# Eagle_DriveUnit_B-series_ver1_0.net
KiCad netlist of a schematic drawn in EAGLE
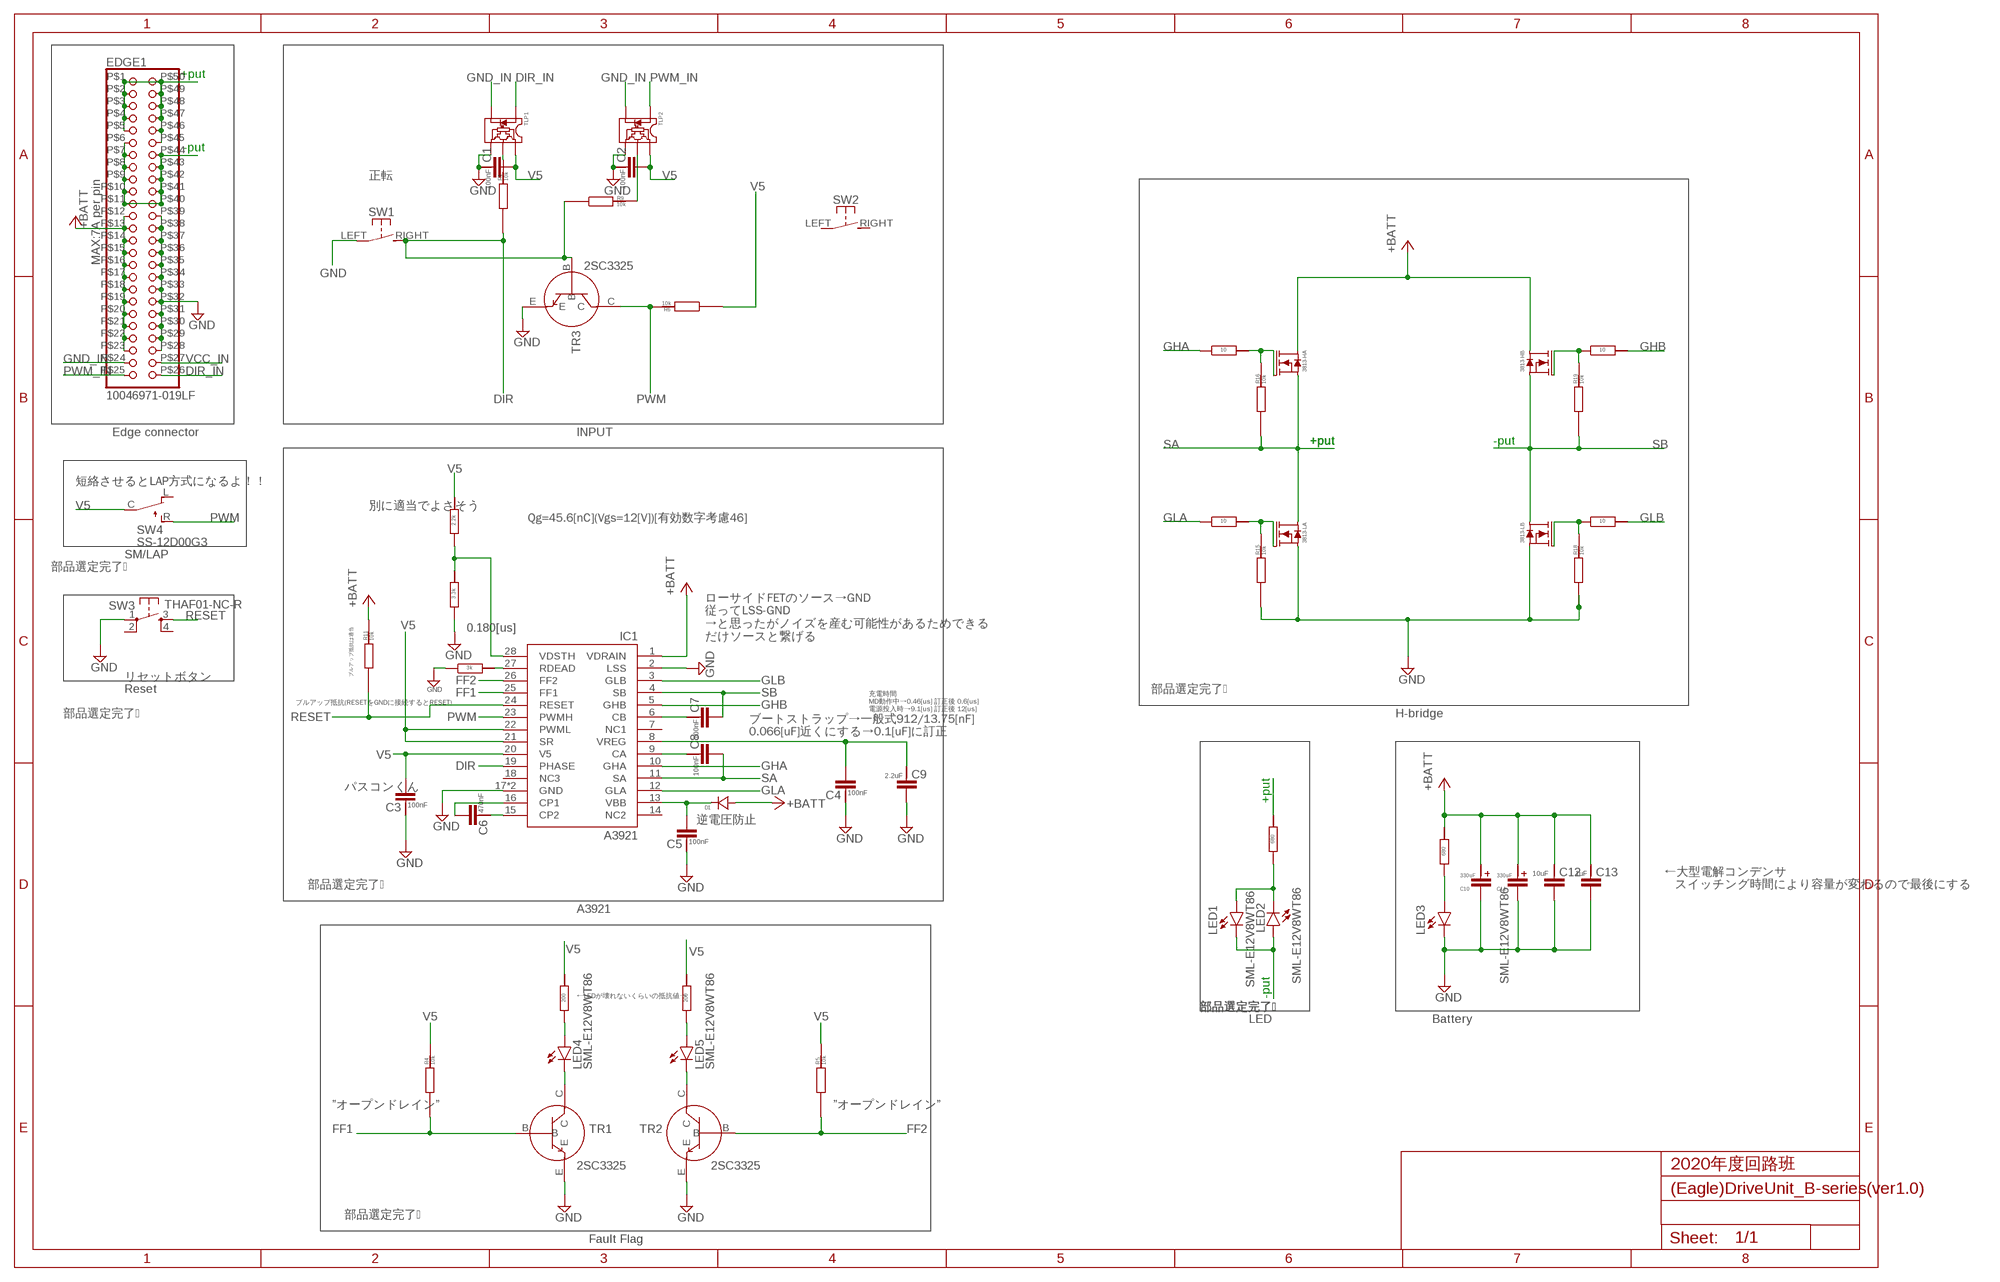
[diagram p0: schematic, sheet 1]

(export (version "E")
  (design (tool "Eeschema 10.0.6"))
  (components
    (comp (ref "3813-HA")
      (value "IRLB3813NOHOLE")
      (footprint "eagle-import:TO-220AB-NOHOLE")
      (libsource (lib "eagle-import") (part "IRLB3813NOHOLE"))
    )
    (comp (ref "3813-HB")
      (value "IRLB3813NOHOLE")
      (footprint "eagle-import:TO-220AB-NOHOLE")
      (libsource (lib "eagle-import") (part "IRLB3813NOHOLE"))
    )
    (comp (ref "3813-LA")
      (value "IRLB3813NOHOLE")
      (footprint "eagle-import:TO-220AB-NOHOLE")
      (libsource (lib "eagle-import") (part "IRLB3813NOHOLE"))
    )
    (comp (ref "3813-LB")
      (value "IRLB3813NOHOLE")
      (footprint "eagle-import:TO-220AB-NOHOLE")
      (libsource (lib "eagle-import") (part "IRLB3813NOHOLE"))
    )
    (comp (ref "C1")
      (value "GCM188L81H104KA57")
      (footprint "eagle-import:GCM188L81H104KA57")
      (libsource (lib "eagle-import") (part "GCM188L81H104KA57"))
    )
    (comp (ref "C2")
      (value "GCM188L81H104KA57")
      (footprint "eagle-import:GCM188L81H104KA57")
      (libsource (lib "eagle-import") (part "GCM188L81H104KA57"))
    )
    (comp (ref "C3")
      (value "GCM188L81H104KA57")
      (footprint "eagle-import:GCM188L81H104KA57")
      (libsource (lib "eagle-import") (part "GCM188L81H104KA57"))
    )
    (comp (ref "C4")
      (value "GCM188L81H104KA57")
      (footprint "eagle-import:GCM188L81H104KA57")
      (libsource (lib "eagle-import") (part "GCM188L81H104KA57"))
    )
    (comp (ref "C5")
      (value "GCM188L81H104KA57")
      (footprint "eagle-import:GCM188L81H104KA57")
      (libsource (lib "eagle-import") (part "GCM188L81H104KA57"))
    )
    (comp (ref "C6")
      (value "GCM21BR71H474KA55")
      (footprint "eagle-import:GCM21BR71H474KA55")
      (libsource (lib "eagle-import") (part "GCM21BR71H474KA55"))
    )
    (comp (ref "C7")
      (value "GCM188L81H104KA57")
      (footprint "eagle-import:GCM188L81H104KA57")
      (libsource (lib "eagle-import") (part "GCM188L81H104KA57"))
    )
    (comp (ref "C8")
      (value "GCM188L81H104KA57")
      (footprint "eagle-import:GCM188L81H104KA57")
      (libsource (lib "eagle-import") (part "GCM188L81H104KA57"))
    )
    (comp (ref "C9")
      (value "GRT31CC81H225KE01L")
      (footprint "eagle-import:GRT31CC81H225KE01L")
      (libsource (lib "eagle-import") (part "GRT31CC81H225KE01L"))
    )
    (comp (ref "C10")
      (value "35PZJ330M10X9")
      (footprint "eagle-import:35PZJ330M10X9")
      (libsource (lib "eagle-import") (part "35PZJ330M10X9"))
    )
    (comp (ref "C11")
      (value "35PZJ330M10X9")
      (footprint "eagle-import:35PZJ330M10X9")
      (libsource (lib "eagle-import") (part "35PZJ330M10X9"))
    )
    (comp (ref "C12")
      (value "GRM32ER7YA106KA12")
      (footprint "eagle-import:GRM32ER7YA106KA12")
      (libsource (lib "eagle-import") (part "GRM32ER7YA106KA12"))
    )
    (comp (ref "C13")
      (value "GRM21BC72A105KE01")
      (footprint "eagle-import:GRM21BC72A105KE01")
      (libsource (lib "eagle-import") (part "GRM21BC72A105KE01"))
    )
    (comp (ref "D1")
      (value "GS1010FL")
      (footprint "eagle-import:GS1010FL")
      (libsource (lib "eagle-import") (part "GS1010FL"))
    )
    (comp (ref "EDGE1")
      (value "10046971-019LF")
      (footprint "eagle-import:10046971-019LF")
      (libsource (lib "eagle-import") (part "10046971-019LF"))
    )
    (comp (ref "IC1")
      (value "A3921")
      (footprint "eagle-import:A3921")
      (libsource (lib "eagle-import") (part "A3921"))
    )
    (comp (ref "LED1")
      (value "SML-E12V8WT86")
      (footprint "eagle-import:SML-E12V8WT86")
      (libsource (lib "eagle-import") (part "SML-E12V8WT86"))
    )
    (comp (ref "LED2")
      (value "SML-E12V8WT86")
      (footprint "eagle-import:SML-E12V8WT86")
      (libsource (lib "eagle-import") (part "SML-E12V8WT86"))
    )
    (comp (ref "LED3")
      (value "SML-E12V8WT86")
      (footprint "eagle-import:SML-E12V8WT86")
      (libsource (lib "eagle-import") (part "SML-E12V8WT86"))
    )
    (comp (ref "LED4")
      (value "SML-E12V8WT86")
      (footprint "eagle-import:SML-E12V8WT86")
      (libsource (lib "eagle-import") (part "SML-E12V8WT86"))
    )
    (comp (ref "LED5")
      (value "SML-E12V8WT86")
      (footprint "eagle-import:SML-E12V8WT86")
      (libsource (lib "eagle-import") (part "SML-E12V8WT86"))
    )
    (comp (ref "R1")
      (value "RG2012")
      (footprint "eagle-import:RG2012")
      (libsource (lib "eagle-import") (part "RG2012"))
    )
    (comp (ref "R2")
      (value "RG2012N-332-W-T1")
      (footprint "eagle-import:RG2012")
      (libsource (lib "eagle-import") (part "RG2012N-332-W-T1"))
    )
    (comp (ref "R3")
      (value "RG2012P-681-B-T5")
      (footprint "eagle-import:RG2012")
      (libsource (lib "eagle-import") (part "RG2012P-681-B-T5"))
    )
    (comp (ref "R4")
      (value "RG2012")
      (footprint "eagle-import:RG2012")
      (libsource (lib "eagle-import") (part "RG2012"))
    )
    (comp (ref "R5")
      (value "RG2012")
      (footprint "eagle-import:RG2012")
      (libsource (lib "eagle-import") (part "RG2012"))
    )
    (comp (ref "R6")
      (value "RG2012")
      (footprint "eagle-import:RG2012")
      (libsource (lib "eagle-import") (part "RG2012"))
    )
    (comp (ref "R7")
      (value "RG2012N-201-W-T1")
      (footprint "eagle-import:RG2012")
      (libsource (lib "eagle-import") (part "RG2012N-201-W-T1"))
    )
    (comp (ref "R8")
      (value "RG2012N-201-W-T1")
      (footprint "eagle-import:RG2012")
      (libsource (lib "eagle-import") (part "RG2012N-201-W-T1"))
    )
    (comp (ref "R9")
      (value "RG2012")
      (footprint "eagle-import:RG2012")
      (libsource (lib "eagle-import") (part "RG2012"))
    )
    (comp (ref "R10")
      (value "RG2012Q-100-D-T5")
      (footprint "eagle-import:RG2012")
      (libsource (lib "eagle-import") (part "RG2012Q-100-D-T5"))
    )
    (comp (ref "R11")
      (value "RG2012")
      (footprint "eagle-import:RG2012")
      (libsource (lib "eagle-import") (part "RG2012"))
    )
    (comp (ref "R12")
      (value "RG2012Q-100-D-T5")
      (footprint "eagle-import:RG2012")
      (libsource (lib "eagle-import") (part "RG2012Q-100-D-T5"))
    )
    (comp (ref "R13")
      (value "RG2012P-302-B-T5")
      (footprint "eagle-import:RG2012")
      (libsource (lib "eagle-import") (part "RG2012P-302-B-T5"))
    )
    (comp (ref "R14")
      (value "RG2012N-222-W-T1")
      (footprint "eagle-import:RG2012")
      (libsource (lib "eagle-import") (part "RG2012N-222-W-T1"))
    )
    (comp (ref "R15")
      (value "RG2012")
      (footprint "eagle-import:RG2012")
      (libsource (lib "eagle-import") (part "RG2012"))
    )
    (comp (ref "R16")
      (value "RG2012")
      (footprint "eagle-import:RG2012")
      (libsource (lib "eagle-import") (part "RG2012"))
    )
    (comp (ref "R18")
      (value "RG2012")
      (footprint "eagle-import:RG2012")
      (libsource (lib "eagle-import") (part "RG2012"))
    )
    (comp (ref "R19")
      (value "RG2012")
      (footprint "eagle-import:RG2012")
      (libsource (lib "eagle-import") (part "RG2012"))
    )
    (comp (ref "R20")
      (value "RG2012Q-100-D-T5")
      (footprint "eagle-import:RG2012")
      (libsource (lib "eagle-import") (part "RG2012Q-100-D-T5"))
    )
    (comp (ref "R21")
      (value "RG2012Q-100-D-T5")
      (footprint "eagle-import:RG2012")
      (libsource (lib "eagle-import") (part "RG2012Q-100-D-T5"))
    )
    (comp (ref "R22")
      (value "RG2012P-681-B-T5")
      (footprint "eagle-import:RG2012")
      (libsource (lib "eagle-import") (part "RG2012P-681-B-T5"))
    )
    (comp (ref "SW1")
      (value "TVAF06-A020B-R")
      (footprint "eagle-import:TVAF06-A020B-R")
      (libsource (lib "eagle-import") (part "TVAF06-A020B-R"))
    )
    (comp (ref "SW2")
      (value "TVAF06-A020B-R")
      (footprint "eagle-import:TVAF06-A020B-R")
      (libsource (lib "eagle-import") (part "TVAF06-A020B-R"))
    )
    (comp (ref "SW3")
      (value "THAF01-NC-R")
      (footprint "eagle-import:THAF01-NC-R")
      (libsource (lib "eagle-import") (part "THAF01-NC-R"))
    )
    (comp (ref "SW4")
      (value "SS-12D00G3")
      (footprint "eagle-import:SS-12D00G3")
      (libsource (lib "eagle-import") (part "SS-12D00G3"))
    )
    (comp (ref "TLP1")
      (value "TLP2366")
      (footprint "eagle-import:TLP2366")
      (libsource (lib "eagle-import") (part "TLP2366"))
    )
    (comp (ref "TLP2")
      (value "TLP2366")
      (footprint "eagle-import:TLP2366")
      (libsource (lib "eagle-import") (part "TLP2366"))
    )
    (comp (ref "TR1")
      (value "2SC3325")
      (footprint "eagle-import:2SC3325")
      (libsource (lib "eagle-import") (part "2SC3325"))
    )
    (comp (ref "TR2")
      (value "2SC3325")
      (footprint "eagle-import:2SC3325")
      (libsource (lib "eagle-import") (part "2SC3325"))
    )
    (comp (ref "TR3")
      (value "2SC3325")
      (footprint "eagle-import:2SC3325")
      (libsource (lib "eagle-import") (part "2SC3325"))
    )
  )
  (nets
    (net (code "1") (name "+BATT") (class "Default")
      (node (ref "3813-HA") (pin "DRAIN") (pinfunction "D_DRAIN") (pintype "passive"))
      (node (ref "3813-HB") (pin "DRAIN") (pinfunction "D_DRAIN") (pintype "passive"))
      (node (ref "C10") (pin "A") (pinfunction "ANODE_A") (pintype "bidirectional"))
      (node (ref "C11") (pin "A") (pinfunction "ANODE_A") (pintype "bidirectional"))
      (node (ref "C12") (pin "P$1") (pinfunction "P$1_P$1") (pintype "bidirectional"))
      (node (ref "C13") (pin "P$1") (pinfunction "P$1_P$1") (pintype "bidirectional"))
      (node (ref "D1") (pin "A") (pinfunction "A_A") (pintype "passive"))
      (node (ref "EDGE1") (pin "P$12") (pinfunction "P12_P$12") (pintype "passive"))
      (node (ref "EDGE1") (pin "P$13") (pinfunction "P13_P$13") (pintype "passive"))
      (node (ref "EDGE1") (pin "P$14") (pinfunction "P14_P$14") (pintype "passive"))
      (node (ref "EDGE1") (pin "P$15") (pinfunction "P15_P$15") (pintype "passive"))
      (node (ref "EDGE1") (pin "P$16") (pinfunction "P16_P$16") (pintype "passive"))
      (node (ref "EDGE1") (pin "P$17") (pinfunction "P17_P$17") (pintype "passive"))
      (node (ref "EDGE1") (pin "P$18") (pinfunction "P18_P$18") (pintype "passive"))
      (node (ref "EDGE1") (pin "P$19") (pinfunction "P19_P$19") (pintype "passive"))
      (node (ref "EDGE1") (pin "P$20") (pinfunction "P20_P$20") (pintype "passive"))
      (node (ref "EDGE1") (pin "P$21") (pinfunction "P21_P$21") (pintype "passive"))
      (node (ref "EDGE1") (pin "P$22") (pinfunction "P22_P$22") (pintype "passive"))
      (node (ref "EDGE1") (pin "P$23") (pinfunction "P23_P$23") (pintype "passive"))
      (node (ref "IC1") (pin "1") (pinfunction "VDRAIN_1") (pintype "bidirectional"))
      (node (ref "R11") (pin "RIGHT") (pinfunction "RIGHT_RIGHT") (pintype "bidirectional"))
      (node (ref "R22") (pin "LEFT") (pinfunction "P$1_LEFT") (pintype "bidirectional"))
    )
    (net (code "2") (name "/DIR") (class "Default")
      (node (ref "IC1") (pin "19") (pinfunction "PHASE_19") (pintype "bidirectional"))
      (node (ref "R1") (pin "LEFT") (pinfunction "LEFT_LEFT") (pintype "bidirectional"))
      (node (ref "R9") (pin "LEFT") (pinfunction "LEFT_LEFT") (pintype "bidirectional"))
      (node (ref "SW1") (pin "RIGHT") (pinfunction "S_RIGHT") (pintype "passive"))
      (node (ref "TR3") (pin "B") (pinfunction "B_B") (pintype "bidirectional"))
    )
    (net (code "3") (name "/DIR_IN") (class "Default")
      (node (ref "EDGE1") (pin "P$26") (pinfunction "P26_P$26") (pintype "passive"))
      (node (ref "TLP1") (pin "1") (pinfunction "ANODE_1") (pintype "passive"))
    )
    (net (code "4") (name "/FF1") (class "Default")
      (node (ref "IC1") (pin "25") (pinfunction "FF1_25") (pintype "bidirectional"))
      (node (ref "R4") (pin "LEFT") (pinfunction "LEFT_LEFT") (pintype "bidirectional"))
      (node (ref "TR1") (pin "B") (pinfunction "B_B") (pintype "bidirectional"))
    )
    (net (code "5") (name "/FF2") (class "Default")
      (node (ref "IC1") (pin "26") (pinfunction "FF2_26") (pintype "bidirectional"))
      (node (ref "R5") (pin "LEFT") (pinfunction "LEFT_LEFT") (pintype "bidirectional"))
      (node (ref "TR2") (pin "B") (pinfunction "B_B") (pintype "bidirectional"))
    )
    (net (code "6") (name "/GHA") (class "Default")
      (node (ref "IC1") (pin "10") (pinfunction "GHA_10") (pintype "bidirectional"))
      (node (ref "R21") (pin "RIGHT") (pinfunction "P$2_RIGHT") (pintype "bidirectional"))
    )
    (net (code "7") (name "/GHB") (class "Default")
      (node (ref "IC1") (pin "5") (pinfunction "GHB_5") (pintype "bidirectional"))
      (node (ref "R12") (pin "LEFT") (pinfunction "P$1_LEFT") (pintype "bidirectional"))
    )
    (net (code "8") (name "/GLA") (class "Default")
      (node (ref "IC1") (pin "12") (pinfunction "GLA_12") (pintype "bidirectional"))
      (node (ref "R20") (pin "RIGHT") (pinfunction "P$2_RIGHT") (pintype "bidirectional"))
    )
    (net (code "9") (name "/GLB") (class "Default")
      (node (ref "IC1") (pin "3") (pinfunction "GLB_3") (pintype "bidirectional"))
      (node (ref "R10") (pin "LEFT") (pinfunction "P$1_LEFT") (pintype "bidirectional"))
    )
    (net (code "10") (name "/GND_IN") (class "Default")
      (node (ref "EDGE1") (pin "P$24") (pinfunction "P24_P$24") (pintype "passive"))
      (node (ref "TLP1") (pin "3") (pinfunction "CATHODE_3") (pintype "passive"))
      (node (ref "TLP2") (pin "3") (pinfunction "CATHODE_3") (pintype "passive"))
    )
    (net (code "11") (name "/PWM") (class "Default")
      (node (ref "IC1") (pin "23") (pinfunction "PWMH_23") (pintype "bidirectional"))
      (node (ref "R6") (pin "RIGHT") (pinfunction "RIGHT_RIGHT") (pintype "bidirectional"))
      (node (ref "SW4") (pin "R") (pinfunction "R_R") (pintype "passive"))
      (node (ref "TR3") (pin "C") (pinfunction "C_C") (pintype "bidirectional"))
    )
    (net (code "12") (name "/PWM_IN") (class "Default")
      (node (ref "EDGE1") (pin "P$25") (pinfunction "P25_P$25") (pintype "passive"))
      (node (ref "TLP2") (pin "1") (pinfunction "ANODE_1") (pintype "passive"))
    )
    (net (code "13") (name "/RESET") (class "Default")
      (node (ref "IC1") (pin "24") (pinfunction "RESET_24") (pintype "bidirectional"))
      (node (ref "R11") (pin "LEFT") (pinfunction "LEFT_LEFT") (pintype "bidirectional"))
      (node (ref "SW3") (pin "3") (pinfunction "3_3") (pintype "passive"))
    )
    (net (code "14") (name "/SA") (class "Default")
      (node (ref "3813-HA") (pin "SOURCE") (pinfunction "S_SOURCE") (pintype "passive"))
      (node (ref "3813-LA") (pin "DRAIN") (pinfunction "D_DRAIN") (pintype "passive"))
      (node (ref "C8") (pin "P$2") (pinfunction "P$2_P$2") (pintype "bidirectional"))
      (node (ref "EDGE1") (pin "P$1") (pinfunction "P1_P$1") (pintype "passive"))
      (node (ref "EDGE1") (pin "P$2") (pinfunction "P2_P$2") (pintype "passive"))
      (node (ref "EDGE1") (pin "P$3") (pinfunction "P3_P$3") (pintype "passive"))
      (node (ref "EDGE1") (pin "P$4") (pinfunction "P4_P$4") (pintype "passive"))
      (node (ref "EDGE1") (pin "P$45") (pinfunction "P45_P$45") (pintype "passive"))
      (node (ref "EDGE1") (pin "P$46") (pinfunction "P46_P$46") (pintype "passive"))
      (node (ref "EDGE1") (pin "P$47") (pinfunction "P47_P$47") (pintype "passive"))
      (node (ref "EDGE1") (pin "P$48") (pinfunction "P48_P$48") (pintype "passive"))
      (node (ref "EDGE1") (pin "P$49") (pinfunction "P49_P$49") (pintype "passive"))
      (node (ref "EDGE1") (pin "P$5") (pinfunction "P5_P$5") (pintype "passive"))
      (node (ref "EDGE1") (pin "P$50") (pinfunction "P50_P$50") (pintype "passive"))
      (node (ref "IC1") (pin "11") (pinfunction "SA_11") (pintype "bidirectional"))
      (node (ref "R16") (pin "LEFT") (pinfunction "LEFT_LEFT") (pintype "bidirectional"))
      (node (ref "R3") (pin "LEFT") (pinfunction "P$1_LEFT") (pintype "bidirectional"))
    )
    (net (code "15") (name "/SB") (class "Default")
      (node (ref "3813-HB") (pin "SOURCE") (pinfunction "S_SOURCE") (pintype "passive"))
      (node (ref "3813-LB") (pin "DRAIN") (pinfunction "D_DRAIN") (pintype "passive"))
      (node (ref "C7") (pin "P$2") (pinfunction "P$2_P$2") (pintype "bidirectional"))
      (node (ref "EDGE1") (pin "P$10") (pinfunction "P10_P$10") (pintype "passive"))
      (node (ref "EDGE1") (pin "P$11") (pinfunction "P11_P$11") (pintype "passive"))
      (node (ref "EDGE1") (pin "P$40") (pinfunction "P40_P$40") (pintype "passive"))
      (node (ref "EDGE1") (pin "P$41") (pinfunction "P41_P$41") (pintype "passive"))
      (node (ref "EDGE1") (pin "P$42") (pinfunction "P42_P$42") (pintype "passive"))
      (node (ref "EDGE1") (pin "P$43") (pinfunction "P43_P$43") (pintype "passive"))
      (node (ref "EDGE1") (pin "P$44") (pinfunction "P44_P$44") (pintype "passive"))
      (node (ref "EDGE1") (pin "P$6") (pinfunction "P6_P$6") (pintype "passive"))
      (node (ref "EDGE1") (pin "P$7") (pinfunction "P7_P$7") (pintype "passive"))
      (node (ref "EDGE1") (pin "P$8") (pinfunction "P8_P$8") (pintype "passive"))
      (node (ref "EDGE1") (pin "P$9") (pinfunction "P9_P$9") (pintype "passive"))
      (node (ref "IC1") (pin "4") (pinfunction "SB_4") (pintype "bidirectional"))
      (node (ref "LED1") (pin "K") (pinfunction "C_K") (pintype "passive"))
      (node (ref "LED2") (pin "A") (pinfunction "A_A") (pintype "passive"))
      (node (ref "R19") (pin "LEFT") (pinfunction "LEFT_LEFT") (pintype "bidirectional"))
    )
    (net (code "16") (name "/V5") (class "Default")
      (node (ref "C1") (pin "P$2") (pinfunction "P$2_P$2") (pintype "bidirectional"))
      (node (ref "C2") (pin "P$2") (pinfunction "P$2_P$2") (pintype "bidirectional"))
      (node (ref "C3") (pin "P$2") (pinfunction "P$2_P$2") (pintype "bidirectional"))
      (node (ref "IC1") (pin "20") (pinfunction "V5_20") (pintype "bidirectional"))
      (node (ref "IC1") (pin "21") (pinfunction "SR_21") (pintype "bidirectional"))
      (node (ref "IC1") (pin "22") (pinfunction "PWML_22") (pintype "bidirectional"))
      (node (ref "R14") (pin "LEFT") (pinfunction "P$1_LEFT") (pintype "bidirectional"))
      (node (ref "R4") (pin "RIGHT") (pinfunction "RIGHT_RIGHT") (pintype "bidirectional"))
      (node (ref "R5") (pin "RIGHT") (pinfunction "RIGHT_RIGHT") (pintype "bidirectional"))
      (node (ref "R6") (pin "LEFT") (pinfunction "LEFT_LEFT") (pintype "bidirectional"))
      (node (ref "R7") (pin "LEFT") (pinfunction "P$1_LEFT") (pintype "bidirectional"))
      (node (ref "R8") (pin "LEFT") (pinfunction "P$1_LEFT") (pintype "bidirectional"))
      (node (ref "SW4") (pin "C") (pinfunction "C_C") (pintype "passive"))
      (node (ref "TLP1") (pin "6") (pinfunction "VCC_6") (pintype "passive"))
      (node (ref "TLP2") (pin "6") (pinfunction "VCC_6") (pintype "passive"))
    )
    (net (code "17") (name "/VCC_IN") (class "Default")
      (node (ref "EDGE1") (pin "P$27") (pinfunction "P27_P$27") (pintype "passive"))
    )
    (net (code "18") (name "GND") (class "Default")
      (node (ref "3813-LA") (pin "SOURCE") (pinfunction "S_SOURCE") (pintype "passive"))
      (node (ref "3813-LB") (pin "SOURCE") (pinfunction "S_SOURCE") (pintype "passive"))
      (node (ref "C1") (pin "P$1") (pinfunction "P$1_P$1") (pintype "bidirectional"))
      (node (ref "C10") (pin "C") (pinfunction "CATHODE_C") (pintype "bidirectional"))
      (node (ref "C11") (pin "C") (pinfunction "CATHODE_C") (pintype "bidirectional"))
      (node (ref "C12") (pin "P$2") (pinfunction "P$2_P$2") (pintype "bidirectional"))
      (node (ref "C13") (pin "P$2") (pinfunction "P$2_P$2") (pintype "bidirectional"))
      (node (ref "C2") (pin "P$1") (pinfunction "P$1_P$1") (pintype "bidirectional"))
      (node (ref "C3") (pin "P$1") (pinfunction "P$1_P$1") (pintype "bidirectional"))
      (node (ref "C4") (pin "P$1") (pinfunction "P$1_P$1") (pintype "bidirectional"))
      (node (ref "C5") (pin "P$1") (pinfunction "P$1_P$1") (pintype "bidirectional"))
      (node (ref "C9") (pin "P$2") (pinfunction "P$2_P$2") (pintype "bidirectional"))
      (node (ref "EDGE1") (pin "P$28") (pinfunction "P28_P$28") (pintype "passive"))
      (node (ref "EDGE1") (pin "P$29") (pinfunction "P29_P$29") (pintype "passive"))
      (node (ref "EDGE1") (pin "P$30") (pinfunction "P30_P$30") (pintype "passive"))
      (node (ref "EDGE1") (pin "P$31") (pinfunction "P31_P$31") (pintype "passive"))
      (node (ref "EDGE1") (pin "P$32") (pinfunction "P32_P$32") (pintype "passive"))
      (node (ref "EDGE1") (pin "P$33") (pinfunction "P33_P$33") (pintype "passive"))
      (node (ref "EDGE1") (pin "P$34") (pinfunction "P34_P$34") (pintype "passive"))
      (node (ref "EDGE1") (pin "P$35") (pinfunction "P35_P$35") (pintype "passive"))
      (node (ref "EDGE1") (pin "P$36") (pinfunction "P36_P$36") (pintype "passive"))
      (node (ref "EDGE1") (pin "P$37") (pinfunction "P37_P$37") (pintype "passive"))
      (node (ref "EDGE1") (pin "P$38") (pinfunction "P38_P$38") (pintype "passive"))
      (node (ref "EDGE1") (pin "P$39") (pinfunction "P39_P$39") (pintype "passive"))
      (node (ref "IC1") (pin "17") (pinfunction "GND_17") (pintype "bidirectional"))
      (node (ref "IC1") (pin "2") (pinfunction "LSS_2") (pintype "bidirectional"))
      (node (ref "IC1") (pin "PAD") (pinfunction "GND_PAD") (pintype "bidirectional"))
      (node (ref "LED3") (pin "K") (pinfunction "C_K") (pintype "passive"))
      (node (ref "R13") (pin "RIGHT") (pinfunction "P$2_RIGHT") (pintype "bidirectional"))
      (node (ref "R15") (pin "LEFT") (pinfunction "LEFT_LEFT") (pintype "bidirectional"))
      (node (ref "R18") (pin "LEFT") (pinfunction "LEFT_LEFT") (pintype "bidirectional"))
      (node (ref "R2") (pin "RIGHT") (pinfunction "P$2_RIGHT") (pintype "bidirectional"))
      (node (ref "SW1") (pin "LEFT") (pinfunction "P_LEFT") (pintype "passive"))
      (node (ref "SW3") (pin "1") (pinfunction "1_1") (pintype "passive"))
      (node (ref "TLP1") (pin "4") (pinfunction "GND_4") (pintype "passive"))
      (node (ref "TLP2") (pin "4") (pinfunction "GND_4") (pintype "passive"))
      (node (ref "TR1") (pin "E") (pinfunction "E_E") (pintype "bidirectional"))
      (node (ref "TR2") (pin "E") (pinfunction "E_E") (pintype "bidirectional"))
      (node (ref "TR3") (pin "E") (pinfunction "E_E") (pintype "bidirectional"))
    )
    (net (code "19") (name "Net-(3813-HA-G)") (class "Default")
      (node (ref "3813-HA") (pin "GATE") (pinfunction "G_GATE") (pintype "passive"))
      (node (ref "R16") (pin "RIGHT") (pinfunction "RIGHT_RIGHT") (pintype "bidirectional"))
      (node (ref "R21") (pin "LEFT") (pinfunction "P$1_LEFT") (pintype "bidirectional"))
    )
    (net (code "20") (name "Net-(3813-HB-G)") (class "Default")
      (node (ref "3813-HB") (pin "GATE") (pinfunction "G_GATE") (pintype "passive"))
      (node (ref "R12") (pin "RIGHT") (pinfunction "P$2_RIGHT") (pintype "bidirectional"))
      (node (ref "R19") (pin "RIGHT") (pinfunction "RIGHT_RIGHT") (pintype "bidirectional"))
    )
    (net (code "21") (name "Net-(3813-LA-G)") (class "Default")
      (node (ref "3813-LA") (pin "GATE") (pinfunction "G_GATE") (pintype "passive"))
      (node (ref "R15") (pin "RIGHT") (pinfunction "RIGHT_RIGHT") (pintype "bidirectional"))
      (node (ref "R20") (pin "LEFT") (pinfunction "P$1_LEFT") (pintype "bidirectional"))
    )
    (net (code "22") (name "Net-(3813-LB-G)") (class "Default")
      (node (ref "3813-LB") (pin "GATE") (pinfunction "G_GATE") (pintype "passive"))
      (node (ref "R10") (pin "RIGHT") (pinfunction "P$2_RIGHT") (pintype "bidirectional"))
      (node (ref "R18") (pin "RIGHT") (pinfunction "RIGHT_RIGHT") (pintype "bidirectional"))
    )
    (net (code "23") (name "Net-(IC1-CA)") (class "Default")
      (node (ref "C8") (pin "P$1") (pinfunction "P$1_P$1") (pintype "bidirectional"))
      (node (ref "IC1") (pin "9") (pinfunction "CA_9") (pintype "bidirectional"))
    )
    (net (code "24") (name "Net-(IC1-CB)") (class "Default")
      (node (ref "C7") (pin "P$1") (pinfunction "P$1_P$1") (pintype "bidirectional"))
      (node (ref "IC1") (pin "6") (pinfunction "CB_6") (pintype "bidirectional"))
    )
    (net (code "25") (name "Net-(IC1-CP1)") (class "Default")
      (node (ref "C6") (pin "P$2") (pinfunction "P$2_P$2") (pintype "bidirectional"))
      (node (ref "IC1") (pin "16") (pinfunction "CP1_16") (pintype "bidirectional"))
    )
    (net (code "26") (name "Net-(IC1-CP2)") (class "Default")
      (node (ref "C6") (pin "P$1") (pinfunction "P$1_P$1") (pintype "bidirectional"))
      (node (ref "IC1") (pin "15") (pinfunction "CP2_15") (pintype "bidirectional"))
    )
    (net (code "27") (name "Net-(IC1-RDEAD)") (class "Default")
      (node (ref "IC1") (pin "27") (pinfunction "RDEAD_27") (pintype "bidirectional"))
      (node (ref "R13") (pin "LEFT") (pinfunction "P$1_LEFT") (pintype "bidirectional"))
    )
    (net (code "28") (name "Net-(IC1-VBB)") (class "Default")
      (node (ref "C5") (pin "P$2") (pinfunction "P$2_P$2") (pintype "bidirectional"))
      (node (ref "D1") (pin "C") (pinfunction "C_C") (pintype "passive"))
      (node (ref "IC1") (pin "13") (pinfunction "VBB_13") (pintype "bidirectional"))
    )
    (net (code "29") (name "Net-(IC1-VDSTH)") (class "Default")
      (node (ref "IC1") (pin "28") (pinfunction "VDSTH_28") (pintype "bidirectional"))
      (node (ref "R14") (pin "RIGHT") (pinfunction "P$2_RIGHT") (pintype "bidirectional"))
      (node (ref "R2") (pin "LEFT") (pinfunction "P$1_LEFT") (pintype "bidirectional"))
    )
    (net (code "30") (name "Net-(IC1-VREG)") (class "Default")
      (node (ref "C4") (pin "P$2") (pinfunction "P$2_P$2") (pintype "bidirectional"))
      (node (ref "C9") (pin "P$1") (pinfunction "P$1_P$1") (pintype "bidirectional"))
      (node (ref "IC1") (pin "8") (pinfunction "VREG_8") (pintype "bidirectional"))
    )
    (net (code "31") (name "Net-(LED2-C)") (class "Default")
      (node (ref "LED1") (pin "A") (pinfunction "A_A") (pintype "passive"))
      (node (ref "LED2") (pin "K") (pinfunction "C_K") (pintype "passive"))
      (node (ref "R3") (pin "RIGHT") (pinfunction "P$2_RIGHT") (pintype "bidirectional"))
    )
    (net (code "32") (name "Net-(LED4-C)") (class "Default")
      (node (ref "LED4") (pin "K") (pinfunction "C_K") (pintype "passive"))
      (node (ref "TR1") (pin "C") (pinfunction "C_C") (pintype "bidirectional"))
    )
    (net (code "33") (name "Net-(LED5-C)") (class "Default")
      (node (ref "LED5") (pin "K") (pinfunction "C_K") (pintype "passive"))
      (node (ref "TR2") (pin "C") (pinfunction "C_C") (pintype "bidirectional"))
    )
    (net (code "34") (name "Net-(R7-P$2)") (class "Default")
      (node (ref "LED4") (pin "A") (pinfunction "A_A") (pintype "passive"))
      (node (ref "R7") (pin "RIGHT") (pinfunction "P$2_RIGHT") (pintype "bidirectional"))
    )
    (net (code "35") (name "Net-(R8-P$2)") (class "Default")
      (node (ref "LED5") (pin "A") (pinfunction "A_A") (pintype "passive"))
      (node (ref "R8") (pin "RIGHT") (pinfunction "P$2_RIGHT") (pintype "bidirectional"))
    )
    (net (code "36") (name "Net-(R22-P$2)") (class "Default")
      (node (ref "LED3") (pin "A") (pinfunction "A_A") (pintype "passive"))
      (node (ref "R22") (pin "RIGHT") (pinfunction "P$2_RIGHT") (pintype "bidirectional"))
    )
    (net (code "37") (name "Net-(TLP1-VOUT)") (class "Default")
      (node (ref "R1") (pin "RIGHT") (pinfunction "RIGHT_RIGHT") (pintype "bidirectional"))
      (node (ref "TLP1") (pin "5") (pinfunction "VOUT_5") (pintype "passive"))
    )
    (net (code "38") (name "Net-(TLP2-VOUT)") (class "Default")
      (node (ref "R9") (pin "RIGHT") (pinfunction "RIGHT_RIGHT") (pintype "bidirectional"))
      (node (ref "TLP2") (pin "5") (pinfunction "VOUT_5") (pintype "passive"))
    )
    (net (code "39") (name "unconnected-(IC1-NC1-Pad7)") (class "Default")
      (node (ref "IC1") (pin "7") (pinfunction "NC1_7") (pintype "bidirectional"))
    )
    (net (code "40") (name "unconnected-(IC1-NC2-Pad14)") (class "Default")
      (node (ref "IC1") (pin "14") (pinfunction "NC2_14") (pintype "bidirectional"))
    )
    (net (code "41") (name "unconnected-(IC1-NC3-Pad18)") (class "Default")
      (node (ref "IC1") (pin "18") (pinfunction "NC3_18") (pintype "bidirectional"))
    )
    (net (code "42") (name "unconnected-(SW2-P-PadLEFT)") (class "Default")
      (node (ref "SW2") (pin "LEFT") (pinfunction "P_LEFT") (pintype "passive"))
    )
    (net (code "43") (name "unconnected-(SW2-S-PadRIGHT)") (class "Default")
      (node (ref "SW2") (pin "RIGHT") (pinfunction "S_RIGHT") (pintype "passive"))
    )
    (net (code "44") (name "unconnected-(SW3-Pad2)") (class "Default")
      (node (ref "SW3") (pin "2") (pinfunction "2_2") (pintype "passive"))
    )
    (net (code "45") (name "unconnected-(SW3-Pad4)") (class "Default")
      (node (ref "SW3") (pin "4") (pinfunction "4_4") (pintype "passive"))
    )
    (net (code "46") (name "unconnected-(SW4-PadL)") (class "Default")
      (node (ref "SW4") (pin "L") (pinfunction "L_L") (pintype "passive"))
    )
  )
)
